# ControlVCC.net
KiCad netlist of a schematic drawn in Altium Designer
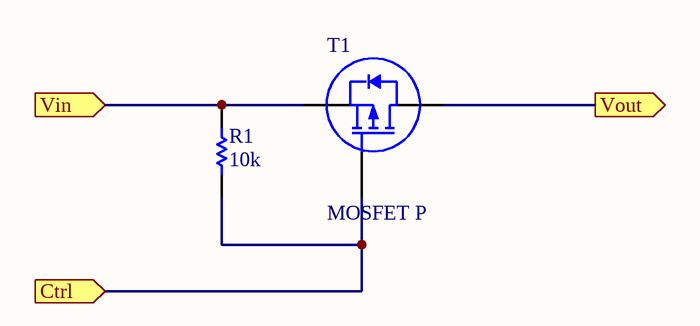
[diagram p0: ControlVCC.SchDoc]

(export (version "E")
  (design (tool "Eeschema 10.0.6"))
  (components
    (comp (ref "R1") (value "10k") (footprint "0805") (libsource (lib "LIBEBAL") (part "RES")))
    (comp (ref "T1") (value "MOSFET P") (footprint "SOT23") (libsource (lib "LIBEBAL") (part "MOSFET P")))
  )
  (nets
    (net (code "1") (name "/Ctrl") (class "Default")
      (node (ref "R1") (pin "1") (pinfunction "1_1") (pintype "passive"))
      (node (ref "T1") (pin "1") (pinfunction "G_1") (pintype "passive"))
    )
    (net (code "2") (name "/Vin") (class "Default")
      (node (ref "R1") (pin "2") (pinfunction "2_2") (pintype "passive"))
      (node (ref "T1") (pin "3") (pinfunction "S_3") (pintype "passive"))
    )
    (net (code "3") (name "/Vout") (class "Default")
      (node (ref "T1") (pin "2") (pinfunction "D_2") (pintype "passive"))
    )
  )
)
